# Node.net
KiCad netlist of a schematic drawn in EAGLE
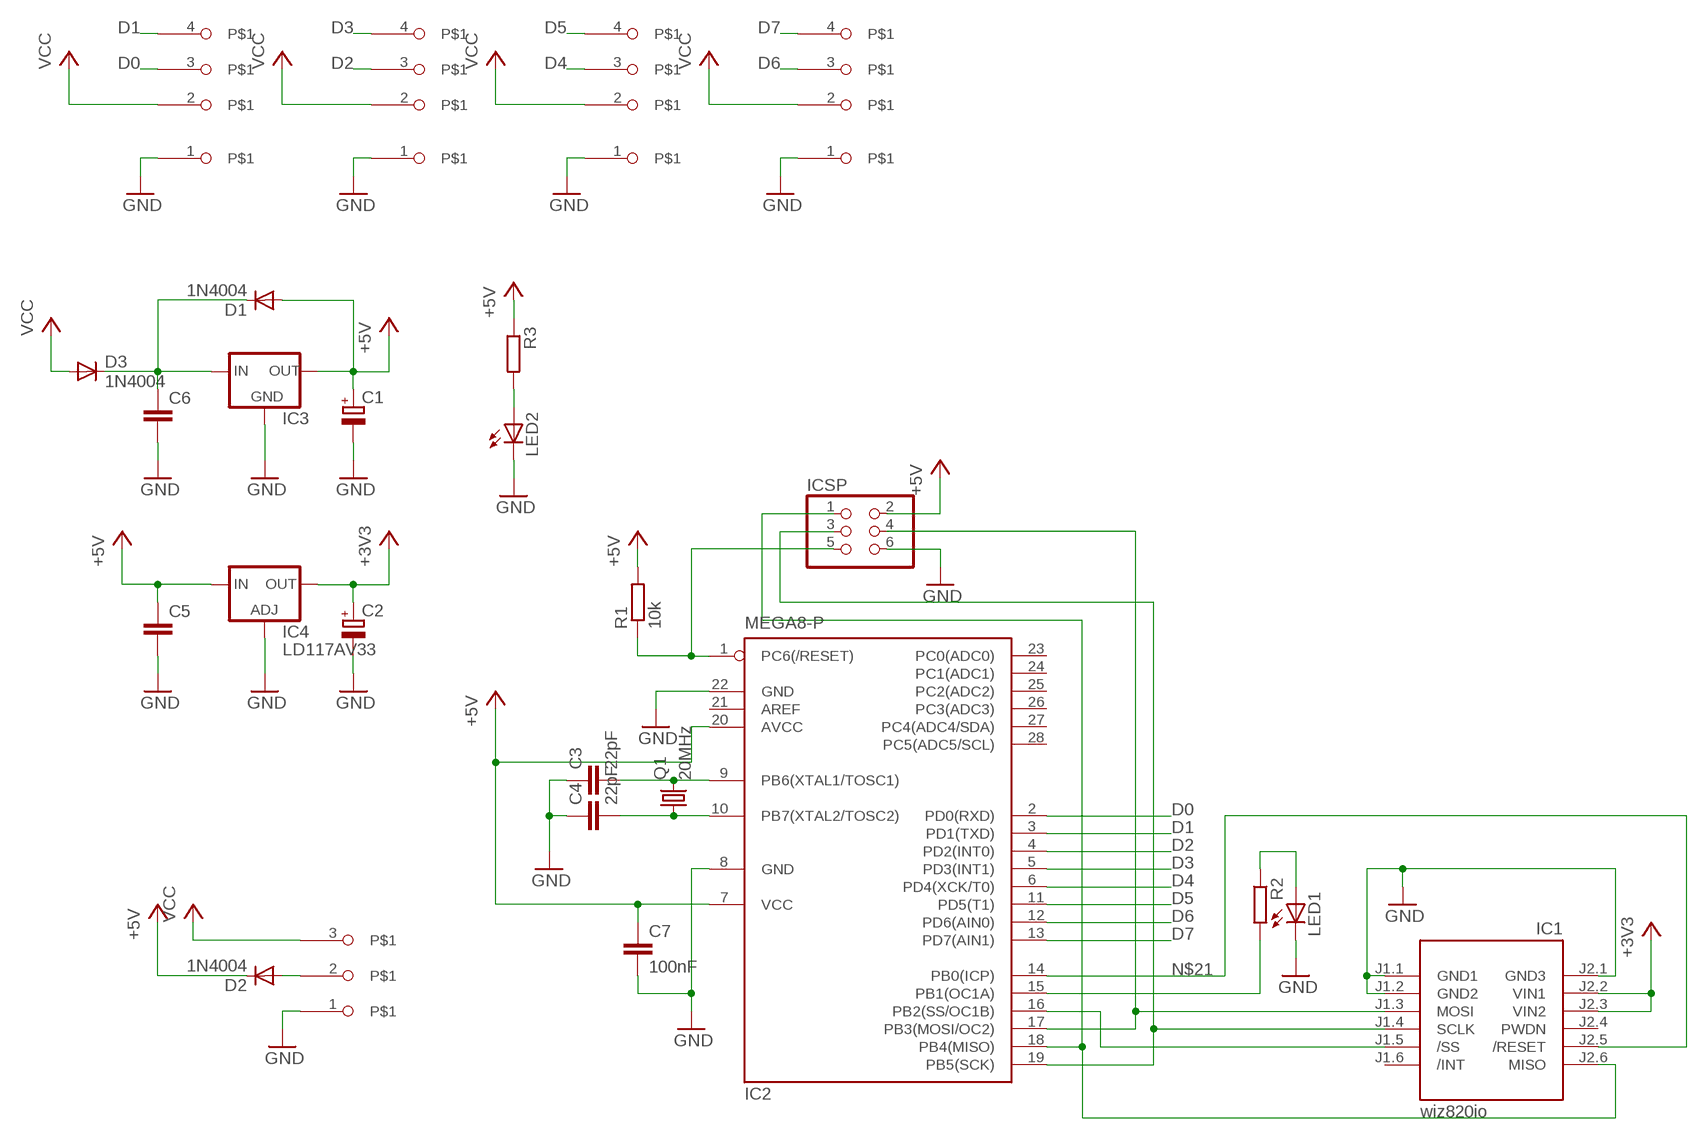
[diagram p0: schematic, sheet 1]

(export (version "E")
  (design (tool "Eeschema 10.0.6"))
  (components
    (comp (ref "C1")
      (value "CPOL-EUE5-10.5")
      (footprint "eagle-import:E5-10,5")
      (libsource (lib "eagle-import") (part "CPOL-EUE5-10.5"))
    )
    (comp (ref "C2")
      (value "CPOL-EUE2.5-6")
      (footprint "eagle-import:E2,5-6")
      (libsource (lib "eagle-import") (part "CPOL-EUE2.5-6"))
    )
    (comp (ref "C3")
      (value "22pF")
      (footprint "eagle-import:C025-025X050")
      (libsource (lib "eagle-import") (part "C-EU025-025X050"))
    )
    (comp (ref "C4")
      (value "22pF")
      (footprint "eagle-import:C025-025X050")
      (libsource (lib "eagle-import") (part "C-EU025-025X050"))
    )
    (comp (ref "C5")
      (value "C-EU025-025X050")
      (footprint "eagle-import:C025-025X050")
      (libsource (lib "eagle-import") (part "C-EU025-025X050"))
    )
    (comp (ref "C6")
      (value "C-EU025-025X050")
      (footprint "eagle-import:C025-025X050")
      (libsource (lib "eagle-import") (part "C-EU025-025X050"))
    )
    (comp (ref "C7")
      (value "100nF")
      (footprint "eagle-import:C025-025X050")
      (libsource (lib "eagle-import") (part "C-EU025-025X050"))
    )
    (comp (ref "D1")
      (value "1N4004")
      (footprint "eagle-import:DO41-10")
      (libsource (lib "eagle-import") (part "1N4004"))
    )
    (comp (ref "D2")
      (value "1N4004")
      (footprint "eagle-import:DO41-10")
      (libsource (lib "eagle-import") (part "1N4004"))
    )
    (comp (ref "D3")
      (value "1N4004")
      (footprint "eagle-import:DO41-10")
      (libsource (lib "eagle-import") (part "1N4004"))
    )
    (comp (ref "IC1")
      (value "wiz820io")
      (footprint "eagle-import:WIZ820IO")
      (libsource (lib "eagle-import") (part "WIZ820IO_DEVICE'DUAL-IN-LINE'"))
    )
    (comp (ref "IC2")
      (value "MEGA8-P")
      (footprint "eagle-import:DIL28-3")
      (libsource (lib "eagle-import") (part "MEGA8-P"))
    )
    (comp (ref "IC3")
      (value "78XXL")
      (footprint "eagle-import:78XXL")
      (libsource (lib "eagle-import") (part "78XXL"))
    )
    (comp (ref "IC4")
      (value "LD117AV33")
      (footprint "eagle-import:TO220L1")
      (libsource (lib "eagle-import") (part "LD117A?V33"))
    )
    (comp (ref "ICSP")
      (value "PINHD-2X3")
      (footprint "eagle-import:2X03")
      (libsource (lib "eagle-import") (part "PINHD-2X3"))
    )
    (comp (ref "LED1")
      (value "LED3MM")
      (footprint "eagle-import:LED3MM")
      (libsource (lib "eagle-import") (part "LED3MM"))
    )
    (comp (ref "LED2")
      (value "LED3MM")
      (footprint "eagle-import:LED3MM")
      (libsource (lib "eagle-import") (part "LED3MM"))
    )
    (comp (ref "Q1")
      (value "20MHz")
      (footprint "eagle-import:HC49_S")
      (libsource (lib "eagle-import") (part "CRYSTALHC49S"))
    )
    (comp (ref "R1")
      (value "10k")
      (footprint "eagle-import:0207_10")
      (libsource (lib "eagle-import") (part "R-EU_0207/10"))
    )
    (comp (ref "R2")
      (value "R-EU_0207/10")
      (footprint "eagle-import:0207_10")
      (libsource (lib "eagle-import") (part "R-EU_0207/10"))
    )
    (comp (ref "R3")
      (value "R-EU_0207/10")
      (footprint "eagle-import:0207_10")
      (libsource (lib "eagle-import") (part "R-EU_0207/10"))
    )
    (comp (ref "U$1")
      (value "691322110004")
      (footprint "eagle-import:691322110004")
      (libsource (lib "eagle-import") (part "691322110004"))
    )
    (comp (ref "U$2")
      (value "691322110004")
      (footprint "eagle-import:691322110004")
      (libsource (lib "eagle-import") (part "691322110004"))
    )
    (comp (ref "U$3")
      (value "691322110004")
      (footprint "eagle-import:691322110004")
      (libsource (lib "eagle-import") (part "691322110004"))
    )
    (comp (ref "U$4")
      (value "691322110004")
      (footprint "eagle-import:691322110004")
      (libsource (lib "eagle-import") (part "691322110004"))
    )
    (comp (ref "U$5")
      (value "CTB9358/3")
      (footprint "eagle-import:CTB9358_3")
      (libsource (lib "eagle-import") (part "CTB9358/3"))
    )
  )
  (nets
    (net (code "1") (name "+3V3") (class "Default")
      (node (ref "C2") (pin "+") (pinfunction "+_+") (pintype "passive"))
      (node (ref "IC1") (pin "J2.2") (pinfunction "VIN1_J2.2") (pintype "power_in"))
      (node (ref "IC1") (pin "J2.3") (pinfunction "VIN2_J2.3") (pintype "power_in"))
      (node (ref "IC4") (pin "2") (pinfunction "OUT_2") (pintype "passive"))
    )
    (net (code "2") (name "+5V") (class "Default")
      (node (ref "C1") (pin "+") (pinfunction "+_+") (pintype "passive"))
      (node (ref "C5") (pin "1") (pinfunction "1_1") (pintype "passive"))
      (node (ref "C7") (pin "1") (pinfunction "1_1") (pintype "passive"))
      (node (ref "D1") (pin "A") (pinfunction "A_A") (pintype "passive"))
      (node (ref "D2") (pin "C") (pinfunction "C_C") (pintype "passive"))
      (node (ref "IC2") (pin "20") (pinfunction "AVCC_20") (pintype "power_in"))
      (node (ref "IC2") (pin "7") (pinfunction "VCC_7") (pintype "power_in"))
      (node (ref "IC3") (pin "OUT") (pinfunction "OUT_OUT") (pintype "passive"))
      (node (ref "IC4") (pin "3") (pinfunction "IN_3") (pintype "input"))
      (node (ref "ICSP") (pin "2") (pinfunction "2_2") (pintype "passive"))
      (node (ref "R1") (pin "2") (pinfunction "2_2") (pintype "passive"))
      (node (ref "R3") (pin "1") (pinfunction "1_1") (pintype "passive"))
    )
    (net (code "3") (name "/D0") (class "Default")
      (node (ref "IC2") (pin "2") (pinfunction "PD0(RXD)_2") (pintype "bidirectional"))
      (node (ref "U$1") (pin "3") (pinfunction "P$1_3") (pintype "bidirectional"))
    )
    (net (code "4") (name "/D1") (class "Default")
      (node (ref "IC2") (pin "3") (pinfunction "PD1(TXD)_3") (pintype "bidirectional"))
      (node (ref "U$1") (pin "4") (pinfunction "P$1_4") (pintype "bidirectional"))
    )
    (net (code "5") (name "/D2") (class "Default")
      (node (ref "IC2") (pin "4") (pinfunction "PD2(INT0)_4") (pintype "bidirectional"))
      (node (ref "U$2") (pin "3") (pinfunction "P$1_3") (pintype "bidirectional"))
    )
    (net (code "6") (name "/D3") (class "Default")
      (node (ref "IC2") (pin "5") (pinfunction "PD3(INT1)_5") (pintype "bidirectional"))
      (node (ref "U$2") (pin "4") (pinfunction "P$1_4") (pintype "bidirectional"))
    )
    (net (code "7") (name "/D4") (class "Default")
      (node (ref "IC2") (pin "6") (pinfunction "PD4(XCK/T0)_6") (pintype "bidirectional"))
      (node (ref "U$3") (pin "3") (pinfunction "P$1_3") (pintype "bidirectional"))
    )
    (net (code "8") (name "/D5") (class "Default")
      (node (ref "IC2") (pin "11") (pinfunction "PD5(T1)_11") (pintype "bidirectional"))
      (node (ref "U$3") (pin "4") (pinfunction "P$1_4") (pintype "bidirectional"))
    )
    (net (code "9") (name "/D6") (class "Default")
      (node (ref "IC2") (pin "12") (pinfunction "PD6(AIN0)_12") (pintype "bidirectional"))
      (node (ref "U$4") (pin "3") (pinfunction "P$1_3") (pintype "bidirectional"))
    )
    (net (code "10") (name "/D7") (class "Default")
      (node (ref "IC2") (pin "13") (pinfunction "PD7(AIN1)_13") (pintype "bidirectional"))
      (node (ref "U$4") (pin "4") (pinfunction "P$1_4") (pintype "bidirectional"))
    )
    (net (code "11") (name "/N$21") (class "Default")
      (node (ref "IC1") (pin "J2.5") (pinfunction "/RESET_J2.5") (pintype "input"))
      (node (ref "IC2") (pin "14") (pinfunction "PB0(ICP)_14") (pintype "bidirectional"))
    )
    (net (code "12") (name "GND") (class "Default")
      (node (ref "C1") (pin "-") (pinfunction "-_-") (pintype "passive"))
      (node (ref "C2") (pin "-") (pinfunction "-_-") (pintype "passive"))
      (node (ref "C3") (pin "1") (pinfunction "1_1") (pintype "passive"))
      (node (ref "C4") (pin "1") (pinfunction "1_1") (pintype "passive"))
      (node (ref "C5") (pin "2") (pinfunction "2_2") (pintype "passive"))
      (node (ref "C6") (pin "2") (pinfunction "2_2") (pintype "passive"))
      (node (ref "C7") (pin "2") (pinfunction "2_2") (pintype "passive"))
      (node (ref "IC1") (pin "J1.1") (pinfunction "GND1_J1.1") (pintype "power_in"))
      (node (ref "IC1") (pin "J1.2") (pinfunction "GND2_J1.2") (pintype "power_in"))
      (node (ref "IC1") (pin "J2.1") (pinfunction "GND3_J2.1") (pintype "power_in"))
      (node (ref "IC2") (pin "22") (pinfunction "GND_22") (pintype "power_in"))
      (node (ref "IC2") (pin "8") (pinfunction "GND_8") (pintype "power_in"))
      (node (ref "IC3") (pin "GND") (pinfunction "GND_GND") (pintype "input"))
      (node (ref "IC4") (pin "1") (pinfunction "ADJ_1") (pintype "input"))
      (node (ref "ICSP") (pin "6") (pinfunction "6_6") (pintype "passive"))
      (node (ref "LED1") (pin "K") (pinfunction "C_K") (pintype "passive"))
      (node (ref "LED2") (pin "K") (pinfunction "C_K") (pintype "passive"))
      (node (ref "U$1") (pin "1") (pinfunction "P$1_1") (pintype "bidirectional"))
      (node (ref "U$2") (pin "1") (pinfunction "P$1_1") (pintype "bidirectional"))
      (node (ref "U$3") (pin "1") (pinfunction "P$1_1") (pintype "bidirectional"))
      (node (ref "U$4") (pin "1") (pinfunction "P$1_1") (pintype "bidirectional"))
      (node (ref "U$5") (pin "1") (pinfunction "P$1_1") (pintype "bidirectional"))
    )
    (net (code "13") (name "Net-(C6-Pad1)") (class "Default")
      (node (ref "C6") (pin "1") (pinfunction "1_1") (pintype "passive"))
      (node (ref "D1") (pin "C") (pinfunction "C_C") (pintype "passive"))
      (node (ref "D3") (pin "C") (pinfunction "C_C") (pintype "passive"))
      (node (ref "IC3") (pin "IN") (pinfunction "IN_IN") (pintype "input"))
    )
    (net (code "14") (name "Net-(IC1-MISO)") (class "Default")
      (node (ref "IC1") (pin "J2.6") (pinfunction "MISO_J2.6") (pintype "output"))
      (node (ref "IC2") (pin "18") (pinfunction "PB4(MISO)_18") (pintype "bidirectional"))
      (node (ref "ICSP") (pin "1") (pinfunction "1_1") (pintype "passive"))
    )
    (net (code "15") (name "Net-(IC1-MOSI)") (class "Default")
      (node (ref "IC1") (pin "J1.3") (pinfunction "MOSI_J1.3") (pintype "input"))
      (node (ref "IC2") (pin "17") (pinfunction "PB3(MOSI/OC2)_17") (pintype "bidirectional"))
      (node (ref "ICSP") (pin "4") (pinfunction "4_4") (pintype "passive"))
    )
    (net (code "16") (name "Net-(IC1-SCLK)") (class "Default")
      (node (ref "IC1") (pin "J1.4") (pinfunction "SCLK_J1.4") (pintype "input"))
      (node (ref "IC2") (pin "19") (pinfunction "PB5(SCK)_19") (pintype "bidirectional"))
      (node (ref "ICSP") (pin "3") (pinfunction "3_3") (pintype "passive"))
    )
    (net (code "17") (name "Net-(IC1-{slash}SS)") (class "Default")
      (node (ref "IC1") (pin "J1.5") (pinfunction "/SS_J1.5") (pintype "input"))
      (node (ref "IC2") (pin "16") (pinfunction "PB2(SS/OC1B)_16") (pintype "bidirectional"))
    )
    (net (code "18") (name "Net-(IC2-PB1(OC1A))") (class "Default")
      (node (ref "IC2") (pin "15") (pinfunction "PB1(OC1A)_15") (pintype "bidirectional"))
      (node (ref "R2") (pin "2") (pinfunction "2_2") (pintype "passive"))
    )
    (net (code "19") (name "Net-(IC2-PB6(XTAL1{slash}TOSC1))") (class "Default")
      (node (ref "C3") (pin "2") (pinfunction "2_2") (pintype "passive"))
      (node (ref "IC2") (pin "9") (pinfunction "PB6(XTAL1/TOSC1)_9") (pintype "bidirectional"))
      (node (ref "Q1") (pin "2") (pinfunction "2_2") (pintype "passive"))
    )
    (net (code "20") (name "Net-(IC2-PB7(XTAL2{slash}TOSC2))") (class "Default")
      (node (ref "C4") (pin "2") (pinfunction "2_2") (pintype "passive"))
      (node (ref "IC2") (pin "10") (pinfunction "PB7(XTAL2/TOSC2)_10") (pintype "bidirectional"))
      (node (ref "Q1") (pin "1") (pinfunction "1_1") (pintype "passive"))
    )
    (net (code "21") (name "Net-(IC2-PC6({slash}RESET))") (class "Default")
      (node (ref "IC2") (pin "1") (pinfunction "PC6(/RESET)_1") (pintype "bidirectional"))
      (node (ref "ICSP") (pin "5") (pinfunction "5_5") (pintype "passive"))
      (node (ref "R1") (pin "1") (pinfunction "1_1") (pintype "passive"))
    )
    (net (code "22") (name "Net-(LED1-PadA)") (class "Default")
      (node (ref "LED1") (pin "A") (pinfunction "A_A") (pintype "passive"))
      (node (ref "R2") (pin "1") (pinfunction "1_1") (pintype "passive"))
    )
    (net (code "23") (name "Net-(LED2-PadA)") (class "Default")
      (node (ref "LED2") (pin "A") (pinfunction "A_A") (pintype "passive"))
      (node (ref "R3") (pin "2") (pinfunction "2_2") (pintype "passive"))
    )
    (net (code "24") (name "Net-(U$5B-P$1)") (class "Default")
      (node (ref "D2") (pin "A") (pinfunction "A_A") (pintype "passive"))
      (node (ref "U$5") (pin "2") (pinfunction "P$1_2") (pintype "bidirectional"))
    )
    (net (code "25") (name "VCC") (class "Default")
      (node (ref "D3") (pin "A") (pinfunction "A_A") (pintype "passive"))
      (node (ref "U$1") (pin "2") (pinfunction "P$1_2") (pintype "bidirectional"))
      (node (ref "U$2") (pin "2") (pinfunction "P$1_2") (pintype "bidirectional"))
      (node (ref "U$3") (pin "2") (pinfunction "P$1_2") (pintype "bidirectional"))
      (node (ref "U$4") (pin "2") (pinfunction "P$1_2") (pintype "bidirectional"))
      (node (ref "U$5") (pin "3") (pinfunction "P$1_3") (pintype "bidirectional"))
    )
    (net (code "26") (name "unconnected-(IC1-PWDN-PadJ2.4)") (class "Default")
      (node (ref "IC1") (pin "J2.4") (pinfunction "PWDN_J2.4") (pintype "input"))
    )
    (net (code "27") (name "unconnected-(IC1-{slash}INT-PadJ1.6)") (class "Default")
      (node (ref "IC1") (pin "J1.6") (pinfunction "/INT_J1.6") (pintype "output"))
    )
    (net (code "28") (name "unconnected-(IC2-AREF-Pad21)") (class "Default")
      (node (ref "IC2") (pin "21") (pinfunction "AREF_21") (pintype "passive"))
    )
    (net (code "29") (name "unconnected-(IC2-PC0(ADC0)-Pad23)") (class "Default")
      (node (ref "IC2") (pin "23") (pinfunction "PC0(ADC0)_23") (pintype "bidirectional"))
    )
    (net (code "30") (name "unconnected-(IC2-PC1(ADC1)-Pad24)") (class "Default")
      (node (ref "IC2") (pin "24") (pinfunction "PC1(ADC1)_24") (pintype "bidirectional"))
    )
    (net (code "31") (name "unconnected-(IC2-PC2(ADC2)-Pad25)") (class "Default")
      (node (ref "IC2") (pin "25") (pinfunction "PC2(ADC2)_25") (pintype "bidirectional"))
    )
    (net (code "32") (name "unconnected-(IC2-PC3(ADC3)-Pad26)") (class "Default")
      (node (ref "IC2") (pin "26") (pinfunction "PC3(ADC3)_26") (pintype "bidirectional"))
    )
    (net (code "33") (name "unconnected-(IC2-PC4(ADC4{slash}SDA)-Pad27)") (class "Default")
      (node (ref "IC2") (pin "27") (pinfunction "PC4(ADC4/SDA)_27") (pintype "bidirectional"))
    )
    (net (code "34") (name "unconnected-(IC2-PC5(ADC5{slash}SCL)-Pad28)") (class "Default")
      (node (ref "IC2") (pin "28") (pinfunction "PC5(ADC5/SCL)_28") (pintype "bidirectional"))
    )
  )
)
